# main.net
KiCad netlist of a schematic drawn in EAGLE
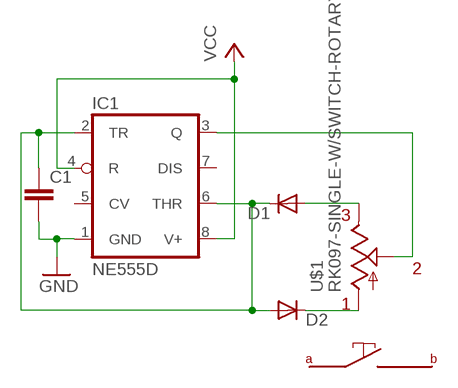
[diagram p0: schematic, sheet 1]

(export (version "E")
  (design (tool "Eeschema 10.0.6"))
  (components
    (comp (ref "C1")
      (value "C-EUC0603")
      (footprint "eagle-import:C0603")
      (libsource (lib "eagle-import") (part "C-EUC0603"))
    )
    (comp (ref "D1")
      (value "DIODE-MICROMELF-W")
      (footprint "eagle-import:MICROMELF-W")
      (libsource (lib "eagle-import") (part "DIODE-MICROMELF-W"))
    )
    (comp (ref "D2")
      (value "DIODE-MICROMELF-W")
      (footprint "eagle-import:MICROMELF-W")
      (libsource (lib "eagle-import") (part "DIODE-MICROMELF-W"))
    )
    (comp (ref "IC1")
      (value "NE555D")
      (footprint "eagle-import:SO08")
      (libsource (lib "eagle-import") (part "555DNE"))
    )
    (comp (ref "U$1")
      (value "RK097-SINGLE-W/SWITCH-ROTARY")
      (footprint "eagle-import:RK097-DUAL-ELEMENT-W_SWITCH")
      (libsource (lib "eagle-import") (part "RK097-SINGLE-W/SWITCH-ROTARY"))
    )
  )
  (nets
    (net (code "1") (name "GND") (class "Default")
      (node (ref "C1") (pin "2") (pinfunction "2_2") (pintype "passive"))
      (node (ref "IC1") (pin "1") (pinfunction "GND_1") (pintype "power_in"))
    )
    (net (code "2") (name "Net-(IC1-Q)") (class "Default")
      (node (ref "IC1") (pin "3") (pinfunction "Q_3") (pintype "output"))
      (node (ref "U$1") (pin "P$5") (pinfunction "S_P$5") (pintype "passive"))
      (node (ref "U$1") (pin "P$6") (pinfunction "S1_P$6") (pintype "passive"))
    )
    (net (code "3") (name "Net-(IC1-THR)") (class "Default")
      (node (ref "C1") (pin "1") (pinfunction "1_1") (pintype "passive"))
      (node (ref "D1") (pin "C") (pinfunction "C_C") (pintype "passive"))
      (node (ref "D2") (pin "A") (pinfunction "A_A") (pintype "passive"))
      (node (ref "IC1") (pin "2") (pinfunction "TR_2") (pintype "input"))
      (node (ref "IC1") (pin "6") (pinfunction "THR_6") (pintype "input"))
    )
    (net (code "4") (name "Net-(U$1-A)") (class "Default")
      (node (ref "D2") (pin "C") (pinfunction "C_C") (pintype "passive"))
      (node (ref "U$1") (pin "P$1") (pinfunction "A_P$1") (pintype "passive"))
      (node (ref "U$1") (pin "P$2") (pinfunction "A1_P$2") (pintype "passive"))
    )
    (net (code "5") (name "Net-(U$1-E)") (class "Default")
      (node (ref "D1") (pin "A") (pinfunction "A_A") (pintype "passive"))
      (node (ref "U$1") (pin "P$3") (pinfunction "E_P$3") (pintype "passive"))
      (node (ref "U$1") (pin "P$4") (pinfunction "E1_P$4") (pintype "passive"))
    )
    (net (code "6") (name "VCC") (class "Default")
      (node (ref "IC1") (pin "4") (pinfunction "R_4") (pintype "input"))
      (node (ref "IC1") (pin "8") (pinfunction "V+_8") (pintype "power_in"))
    )
    (net (code "7") (name "unconnected-(IC1-CV-Pad5)") (class "Default")
      (node (ref "IC1") (pin "5") (pinfunction "CV_5") (pintype "input"))
    )
    (net (code "8") (name "unconnected-(IC1-DIS-Pad7)") (class "Default")
      (node (ref "IC1") (pin "7") (pinfunction "DIS_7") (pintype "input"))
    )
  )
)
